# Filtros.net
KiCad netlist of a schematic drawn in Altium Designer
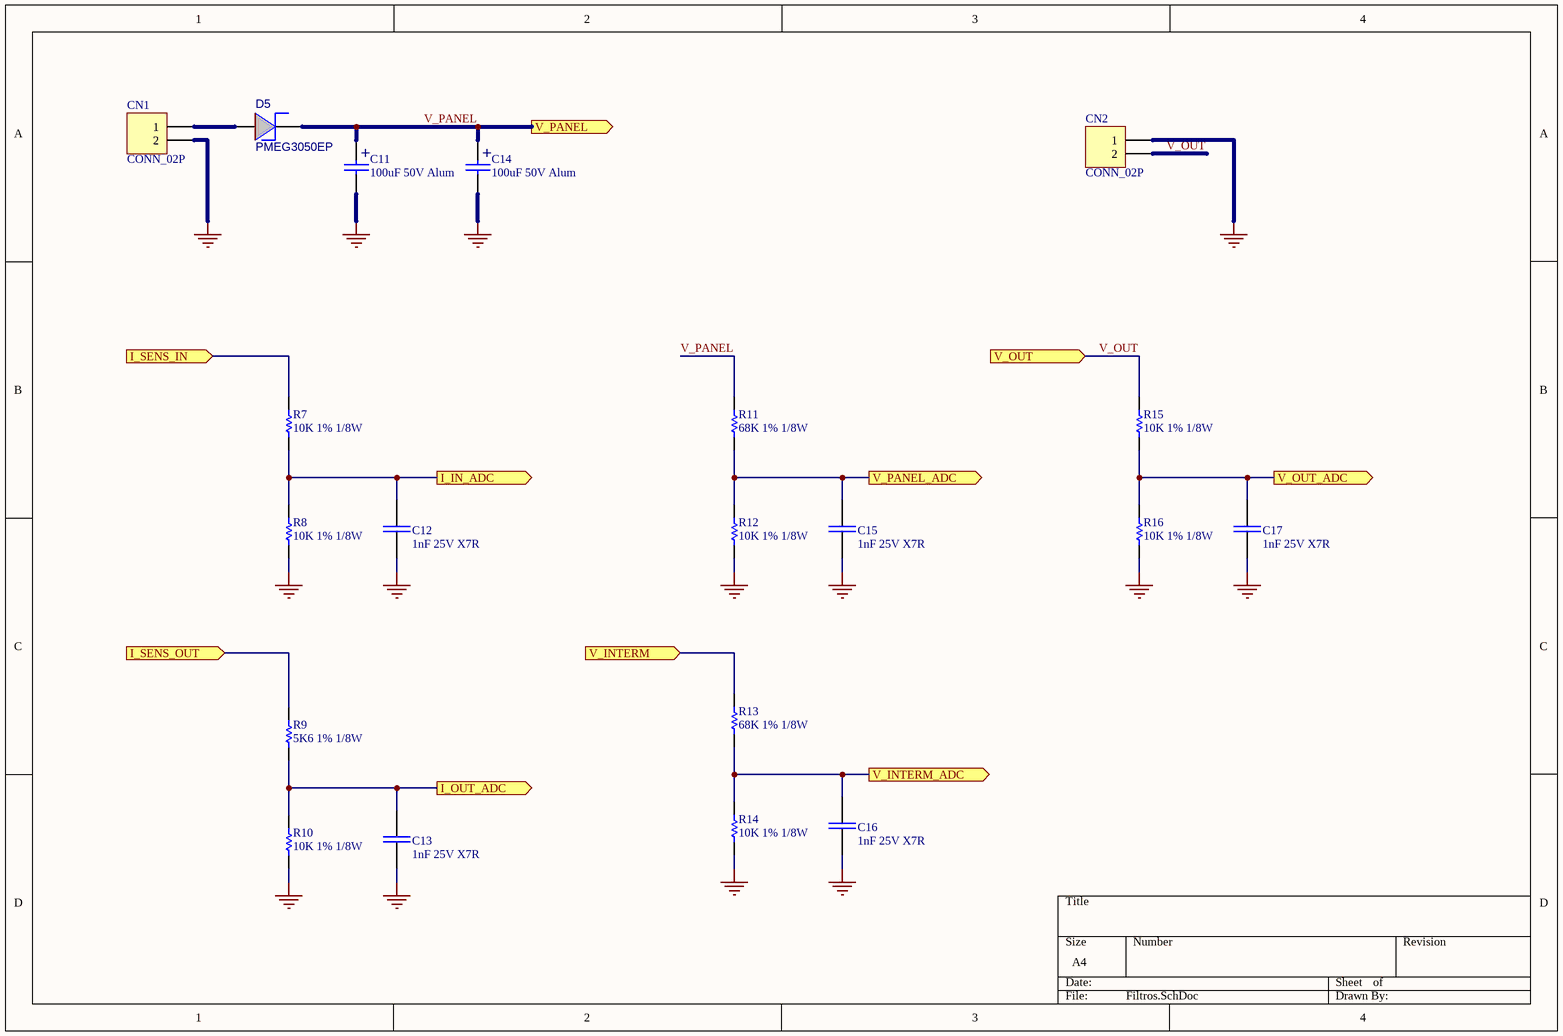
[diagram p0: Filtros.SchDoc]

(export (version "E")
  (design (tool "Eeschema 10.0.6"))
  (components
    (comp (ref "C11")
      (value "100uF 50V Alum")
      (footprint "CAPSMD8x8.3")
      (description "UWZ1H101MCL1GS")
      (libsource (lib "Libreria_Casera") (part "CAPPOL"))
    )
    (comp (ref "C12")
      (value "1nF 25V X7R")
      (footprint "0805")
      (description "Ceramic Capacitor")
      (libsource (lib "MPPTLib") (part "Ceramic capacitor"))
    )
    (comp (ref "C13")
      (value "1nF 25V X7R")
      (footprint "0805")
      (description "Ceramic Capacitor")
      (libsource (lib "MPPTLib") (part "Ceramic capacitor"))
    )
    (comp (ref "C14")
      (value "100uF 50V Alum")
      (footprint "CAPSMD8x8.3")
      (description "UWZ1H101MCL1GS")
      (libsource (lib "Libreria_Casera") (part "CAPPOL"))
    )
    (comp (ref "C15")
      (value "1nF 25V X7R")
      (footprint "0805")
      (description "Ceramic Capacitor")
      (libsource (lib "MPPTLib") (part "Ceramic capacitor"))
    )
    (comp (ref "C16")
      (value "1nF 25V X7R")
      (footprint "0805")
      (description "Ceramic Capacitor")
      (libsource (lib "MPPTLib") (part "Ceramic capacitor"))
    )
    (comp (ref "C17")
      (value "1nF 25V X7R")
      (footprint "0805")
      (description "Ceramic Capacitor")
      (libsource (lib "MPPTLib") (part "Ceramic capacitor"))
    )
    (comp (ref "CN1")
      (value "CONN_02P")
      (footprint "Bornera2_DegsonH")
      (description "Connector Generic 2 Vias")
      (libsource (lib "MPPTLib") (part "CONN_02P"))
    )
    (comp (ref "CN2")
      (value "CONN_02P")
      (footprint "Bornera2_DegsonH")
      (description "Connector Generic 2 Vias")
      (libsource (lib "MPPTLib") (part "CONN_02P"))
    )
    (comp (ref "D5")
      (value "PMEG3050EP")
      (footprint "SOD-128")
      (description "Diode Shottky")
      (libsource (lib "MPPTLib") (part "DIODO_SH"))
    )
    (comp (ref "R7")
      (value "10K 1% 1/8W")
      (footprint "0805")
      (libsource (lib "Libreria_Casera") (part "RES"))
    )
    (comp (ref "R8")
      (value "10K 1% 1/8W")
      (footprint "0805")
      (libsource (lib "Libreria_Casera") (part "RES"))
    )
    (comp (ref "R9")
      (value "5K6 1% 1/8W")
      (footprint "0805")
      (libsource (lib "Libreria_Casera") (part "RES"))
    )
    (comp (ref "R10")
      (value "10K 1% 1/8W")
      (footprint "0805")
      (libsource (lib "Libreria_Casera") (part "RES"))
    )
    (comp (ref "R11")
      (value "68K 1% 1/8W")
      (footprint "0805")
      (libsource (lib "Libreria_Casera") (part "RES"))
    )
    (comp (ref "R12")
      (value "10K 1% 1/8W")
      (footprint "0805")
      (libsource (lib "Libreria_Casera") (part "RES"))
    )
    (comp (ref "R13")
      (value "68K 1% 1/8W")
      (footprint "0805")
      (libsource (lib "Libreria_Casera") (part "RES"))
    )
    (comp (ref "R14")
      (value "10K 1% 1/8W")
      (footprint "0805")
      (libsource (lib "Libreria_Casera") (part "RES"))
    )
    (comp (ref "R15")
      (value "10K 1% 1/8W")
      (footprint "0805")
      (libsource (lib "Libreria_Casera") (part "RES"))
    )
    (comp (ref "R16")
      (value "10K 1% 1/8W")
      (footprint "0805")
      (libsource (lib "Libreria_Casera") (part "RES"))
    )
  )
  (nets
    (net (code "1") (name "/I_IN_ADC") (class "Default")
      (node (ref "C12") (pin "1") (pinfunction "1_1") (pintype "passive"))
      (node (ref "R7") (pin "1") (pinfunction "1_1") (pintype "passive"))
      (node (ref "R8") (pin "2") (pinfunction "2_2") (pintype "passive"))
    )
    (net (code "2") (name "/I_OUT_ADC") (class "Default")
      (node (ref "C13") (pin "1") (pinfunction "1_1") (pintype "passive"))
      (node (ref "R10") (pin "2") (pinfunction "2_2") (pintype "passive"))
      (node (ref "R9") (pin "1") (pinfunction "1_1") (pintype "passive"))
    )
    (net (code "3") (name "/I_SENS_IN") (class "Default")
      (node (ref "R7") (pin "2") (pinfunction "2_2") (pintype "passive"))
    )
    (net (code "4") (name "/I_SENS_OUT") (class "Default")
      (node (ref "R9") (pin "2") (pinfunction "2_2") (pintype "passive"))
    )
    (net (code "5") (name "/V_INTERM") (class "Default")
      (node (ref "R13") (pin "2") (pinfunction "2_2") (pintype "passive"))
    )
    (net (code "6") (name "/V_INTERM_ADC") (class "Default")
      (node (ref "C16") (pin "1") (pinfunction "1_1") (pintype "passive"))
      (node (ref "R13") (pin "1") (pinfunction "1_1") (pintype "passive"))
      (node (ref "R14") (pin "2") (pinfunction "2_2") (pintype "passive"))
    )
    (net (code "7") (name "/V_OUT") (class "Default")
      (node (ref "CN2") (pin "2") (pinfunction "2_2") (pintype "passive"))
      (node (ref "R15") (pin "2") (pinfunction "2_2") (pintype "passive"))
    )
    (net (code "8") (name "/V_OUT_ADC") (class "Default")
      (node (ref "C17") (pin "1") (pinfunction "1_1") (pintype "passive"))
      (node (ref "R15") (pin "1") (pinfunction "1_1") (pintype "passive"))
      (node (ref "R16") (pin "2") (pinfunction "2_2") (pintype "passive"))
    )
    (net (code "9") (name "/V_PANEL") (class "Default")
      (node (ref "C11") (pin "1") (pinfunction "1_1") (pintype "passive"))
      (node (ref "C14") (pin "1") (pinfunction "1_1") (pintype "passive"))
      (node (ref "D5") (pin "2") (pinfunction "K_2") (pintype "passive"))
      (node (ref "R11") (pin "2") (pinfunction "2_2") (pintype "passive"))
    )
    (net (code "10") (name "/V_PANEL_ADC") (class "Default")
      (node (ref "C15") (pin "1") (pinfunction "1_1") (pintype "passive"))
      (node (ref "R11") (pin "1") (pinfunction "1_1") (pintype "passive"))
      (node (ref "R12") (pin "2") (pinfunction "2_2") (pintype "passive"))
    )
    (net (code "11") (name "GND") (class "Default")
      (node (ref "C11") (pin "2") (pinfunction "2_2") (pintype "passive"))
      (node (ref "C12") (pin "2") (pinfunction "2_2") (pintype "passive"))
      (node (ref "C13") (pin "2") (pinfunction "2_2") (pintype "passive"))
      (node (ref "C14") (pin "2") (pinfunction "2_2") (pintype "passive"))
      (node (ref "C15") (pin "2") (pinfunction "2_2") (pintype "passive"))
      (node (ref "C16") (pin "2") (pinfunction "2_2") (pintype "passive"))
      (node (ref "C17") (pin "2") (pinfunction "2_2") (pintype "passive"))
      (node (ref "CN1") (pin "2") (pinfunction "2_2") (pintype "passive"))
      (node (ref "CN2") (pin "1") (pinfunction "1_1") (pintype "passive"))
      (node (ref "R10") (pin "1") (pinfunction "1_1") (pintype "passive"))
      (node (ref "R12") (pin "1") (pinfunction "1_1") (pintype "passive"))
      (node (ref "R14") (pin "1") (pinfunction "1_1") (pintype "passive"))
      (node (ref "R16") (pin "1") (pinfunction "1_1") (pintype "passive"))
      (node (ref "R8") (pin "1") (pinfunction "1_1") (pintype "passive"))
    )
    (net (code "12") (name "Net-(D5-A)") (class "Default")
      (node (ref "CN1") (pin "1") (pinfunction "1_1") (pintype "passive"))
      (node (ref "D5") (pin "1") (pinfunction "A_1") (pintype "passive"))
    )
  )
)
